# BD0007.net
KiCad netlist of a schematic drawn in EAGLE
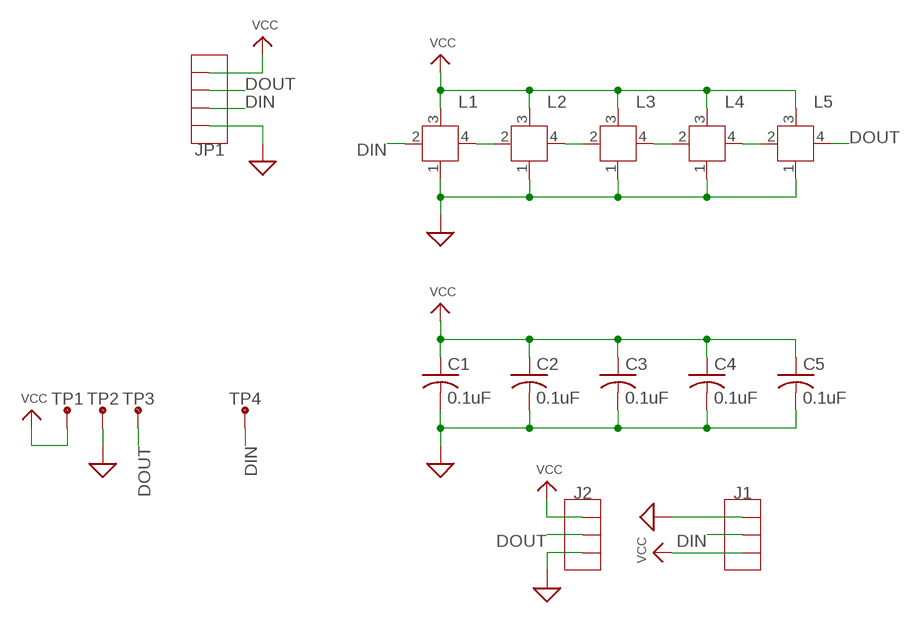
[diagram p0: schematic, sheet 1]

(export (version "E")
  (design (tool "Eeschema 10.0.6"))
  (components
    (comp (ref "C1")
      (value "0.1uF")
      (footprint "eagle-import:C0402")
      (libsource (lib "eagle-import") (part "C-USC0402"))
    )
    (comp (ref "C2")
      (value "0.1uF")
      (footprint "eagle-import:C0402")
      (libsource (lib "eagle-import") (part "C-USC0402"))
    )
    (comp (ref "C3")
      (value "0.1uF")
      (footprint "eagle-import:C0402")
      (libsource (lib "eagle-import") (part "C-USC0402"))
    )
    (comp (ref "C4")
      (value "0.1uF")
      (footprint "eagle-import:C0402")
      (libsource (lib "eagle-import") (part "C-USC0402"))
    )
    (comp (ref "C5")
      (value "0.1uF")
      (footprint "eagle-import:C0402")
      (libsource (lib "eagle-import") (part "C-USC0402"))
    )
    (comp (ref "J1")
      (value "HEADER_1X3MALE")
      (footprint "eagle-import:M3SMD")
      (libsource (lib "eagle-import") (part "HEADER_1X3MALE"))
    )
    (comp (ref "J2")
      (value "HEADER_1X3FEMALE")
      (footprint "eagle-import:F3SMD")
      (libsource (lib "eagle-import") (part "HEADER_1X3FEMALE"))
    )
    (comp (ref "JP1")
      (value "HEADER_1X4S")
      (footprint "eagle-import:1X04")
      (libsource (lib "eagle-import") (part "HEADER_1X4S"))
    )
    (comp (ref "L1")
      (value "WS2812B")
      (footprint "eagle-import:SK6812")
      (libsource (lib "eagle-import") (part "WS2812B"))
    )
    (comp (ref "L2")
      (value "WS2812B")
      (footprint "eagle-import:SK6812")
      (libsource (lib "eagle-import") (part "WS2812B"))
    )
    (comp (ref "L3")
      (value "WS2812B")
      (footprint "eagle-import:SK6812")
      (libsource (lib "eagle-import") (part "WS2812B"))
    )
    (comp (ref "L4")
      (value "WS2812B")
      (footprint "eagle-import:SK6812")
      (libsource (lib "eagle-import") (part "WS2812B"))
    )
    (comp (ref "L5")
      (value "WS2812B")
      (footprint "eagle-import:SK6812")
      (libsource (lib "eagle-import") (part "WS2812B"))
    )
    (comp (ref "TP1")
      (value "VCC")
      (footprint "eagle-import:TEST_POINT")
      (libsource (lib "eagle-import") (part "TEST_POINT"))
    )
    (comp (ref "TP2")
      (value "GND")
      (footprint "eagle-import:TEST_POINT")
      (libsource (lib "eagle-import") (part "TEST_POINT"))
    )
    (comp (ref "TP3")
      (value "DOUT")
      (footprint "eagle-import:TEST_POINT")
      (libsource (lib "eagle-import") (part "TEST_POINT"))
    )
    (comp (ref "TP4")
      (value "DIN")
      (footprint "eagle-import:TEST_POINT")
      (libsource (lib "eagle-import") (part "TEST_POINT"))
    )
  )
  (nets
    (net (code "1") (name "/DIN") (class "Default")
      (node (ref "J1") (pin "2") (pinfunction "P$2_2") (pintype "bidirectional"))
      (node (ref "JP1") (pin "2") (pinfunction "P$2_2") (pintype "bidirectional"))
      (node (ref "L1") (pin "2") (pinfunction "DIN_2") (pintype "bidirectional"))
      (node (ref "TP4") (pin "P$1") (pinfunction "P$1_P$1") (pintype "input"))
    )
    (net (code "2") (name "/DOUT") (class "Default")
      (node (ref "J2") (pin "2A") (pinfunction "P$2_2A") (pintype "bidirectional"))
      (node (ref "J2") (pin "2B") (pinfunction "P$2_2B") (pintype "bidirectional"))
      (node (ref "JP1") (pin "3") (pinfunction "P$3_3") (pintype "bidirectional"))
      (node (ref "L5") (pin "4") (pinfunction "DOUT_4") (pintype "bidirectional"))
      (node (ref "TP3") (pin "P$1") (pinfunction "P$1_P$1") (pintype "input"))
    )
    (net (code "3") (name "Net-(L1-DOUT)") (class "Default")
      (node (ref "L1") (pin "4") (pinfunction "DOUT_4") (pintype "bidirectional"))
      (node (ref "L2") (pin "2") (pinfunction "DIN_2") (pintype "bidirectional"))
    )
    (net (code "4") (name "Net-(L2-DOUT)") (class "Default")
      (node (ref "L2") (pin "4") (pinfunction "DOUT_4") (pintype "bidirectional"))
      (node (ref "L3") (pin "2") (pinfunction "DIN_2") (pintype "bidirectional"))
    )
    (net (code "5") (name "Net-(L3-DOUT)") (class "Default")
      (node (ref "L3") (pin "4") (pinfunction "DOUT_4") (pintype "bidirectional"))
      (node (ref "L4") (pin "2") (pinfunction "DIN_2") (pintype "bidirectional"))
    )
    (net (code "6") (name "Net-(L4-DOUT)") (class "Default")
      (node (ref "L4") (pin "4") (pinfunction "DOUT_4") (pintype "bidirectional"))
      (node (ref "L5") (pin "2") (pinfunction "DIN_2") (pintype "bidirectional"))
    )
    (net (code "7") (name "SUP") (class "Default")
      (node (ref "C1") (pin "2") (pinfunction "2_2") (pintype "passive"))
      (node (ref "C2") (pin "2") (pinfunction "2_2") (pintype "passive"))
      (node (ref "C3") (pin "2") (pinfunction "2_2") (pintype "passive"))
      (node (ref "C4") (pin "2") (pinfunction "2_2") (pintype "passive"))
      (node (ref "C5") (pin "2") (pinfunction "2_2") (pintype "passive"))
      (node (ref "J1") (pin "1") (pinfunction "P$1_1") (pintype "bidirectional"))
      (node (ref "J2") (pin "3A") (pinfunction "P$3_3A") (pintype "bidirectional"))
      (node (ref "J2") (pin "3B") (pinfunction "P$3_3B") (pintype "bidirectional"))
      (node (ref "JP1") (pin "1") (pinfunction "P$1_1") (pintype "bidirectional"))
      (node (ref "L1") (pin "1") (pinfunction "VSS_1") (pintype "bidirectional"))
      (node (ref "L2") (pin "1") (pinfunction "VSS_1") (pintype "bidirectional"))
      (node (ref "L3") (pin "1") (pinfunction "VSS_1") (pintype "bidirectional"))
      (node (ref "L4") (pin "1") (pinfunction "VSS_1") (pintype "bidirectional"))
      (node (ref "L5") (pin "1") (pinfunction "VSS_1") (pintype "bidirectional"))
      (node (ref "TP2") (pin "P$1") (pinfunction "P$1_P$1") (pintype "input"))
    )
    (net (code "8") (name "VCC") (class "Default")
      (node (ref "C1") (pin "1") (pinfunction "1_1") (pintype "passive"))
      (node (ref "C2") (pin "1") (pinfunction "1_1") (pintype "passive"))
      (node (ref "C3") (pin "1") (pinfunction "1_1") (pintype "passive"))
      (node (ref "C4") (pin "1") (pinfunction "1_1") (pintype "passive"))
      (node (ref "C5") (pin "1") (pinfunction "1_1") (pintype "passive"))
      (node (ref "J1") (pin "3") (pinfunction "P$3_3") (pintype "bidirectional"))
      (node (ref "J2") (pin "1A") (pinfunction "P$1_1A") (pintype "bidirectional"))
      (node (ref "J2") (pin "1B") (pinfunction "P$1_1B") (pintype "bidirectional"))
      (node (ref "JP1") (pin "4") (pinfunction "P$4_4") (pintype "bidirectional"))
      (node (ref "L1") (pin "3") (pinfunction "VDD_3") (pintype "bidirectional"))
      (node (ref "L2") (pin "3") (pinfunction "VDD_3") (pintype "bidirectional"))
      (node (ref "L3") (pin "3") (pinfunction "VDD_3") (pintype "bidirectional"))
      (node (ref "L4") (pin "3") (pinfunction "VDD_3") (pintype "bidirectional"))
      (node (ref "L5") (pin "3") (pinfunction "VDD_3") (pintype "bidirectional"))
      (node (ref "TP1") (pin "P$1") (pinfunction "P$1_P$1") (pintype "input"))
    )
  )
)
